# Schematics_Design.net
KiCad netlist of a schematic drawn in EasyEDA
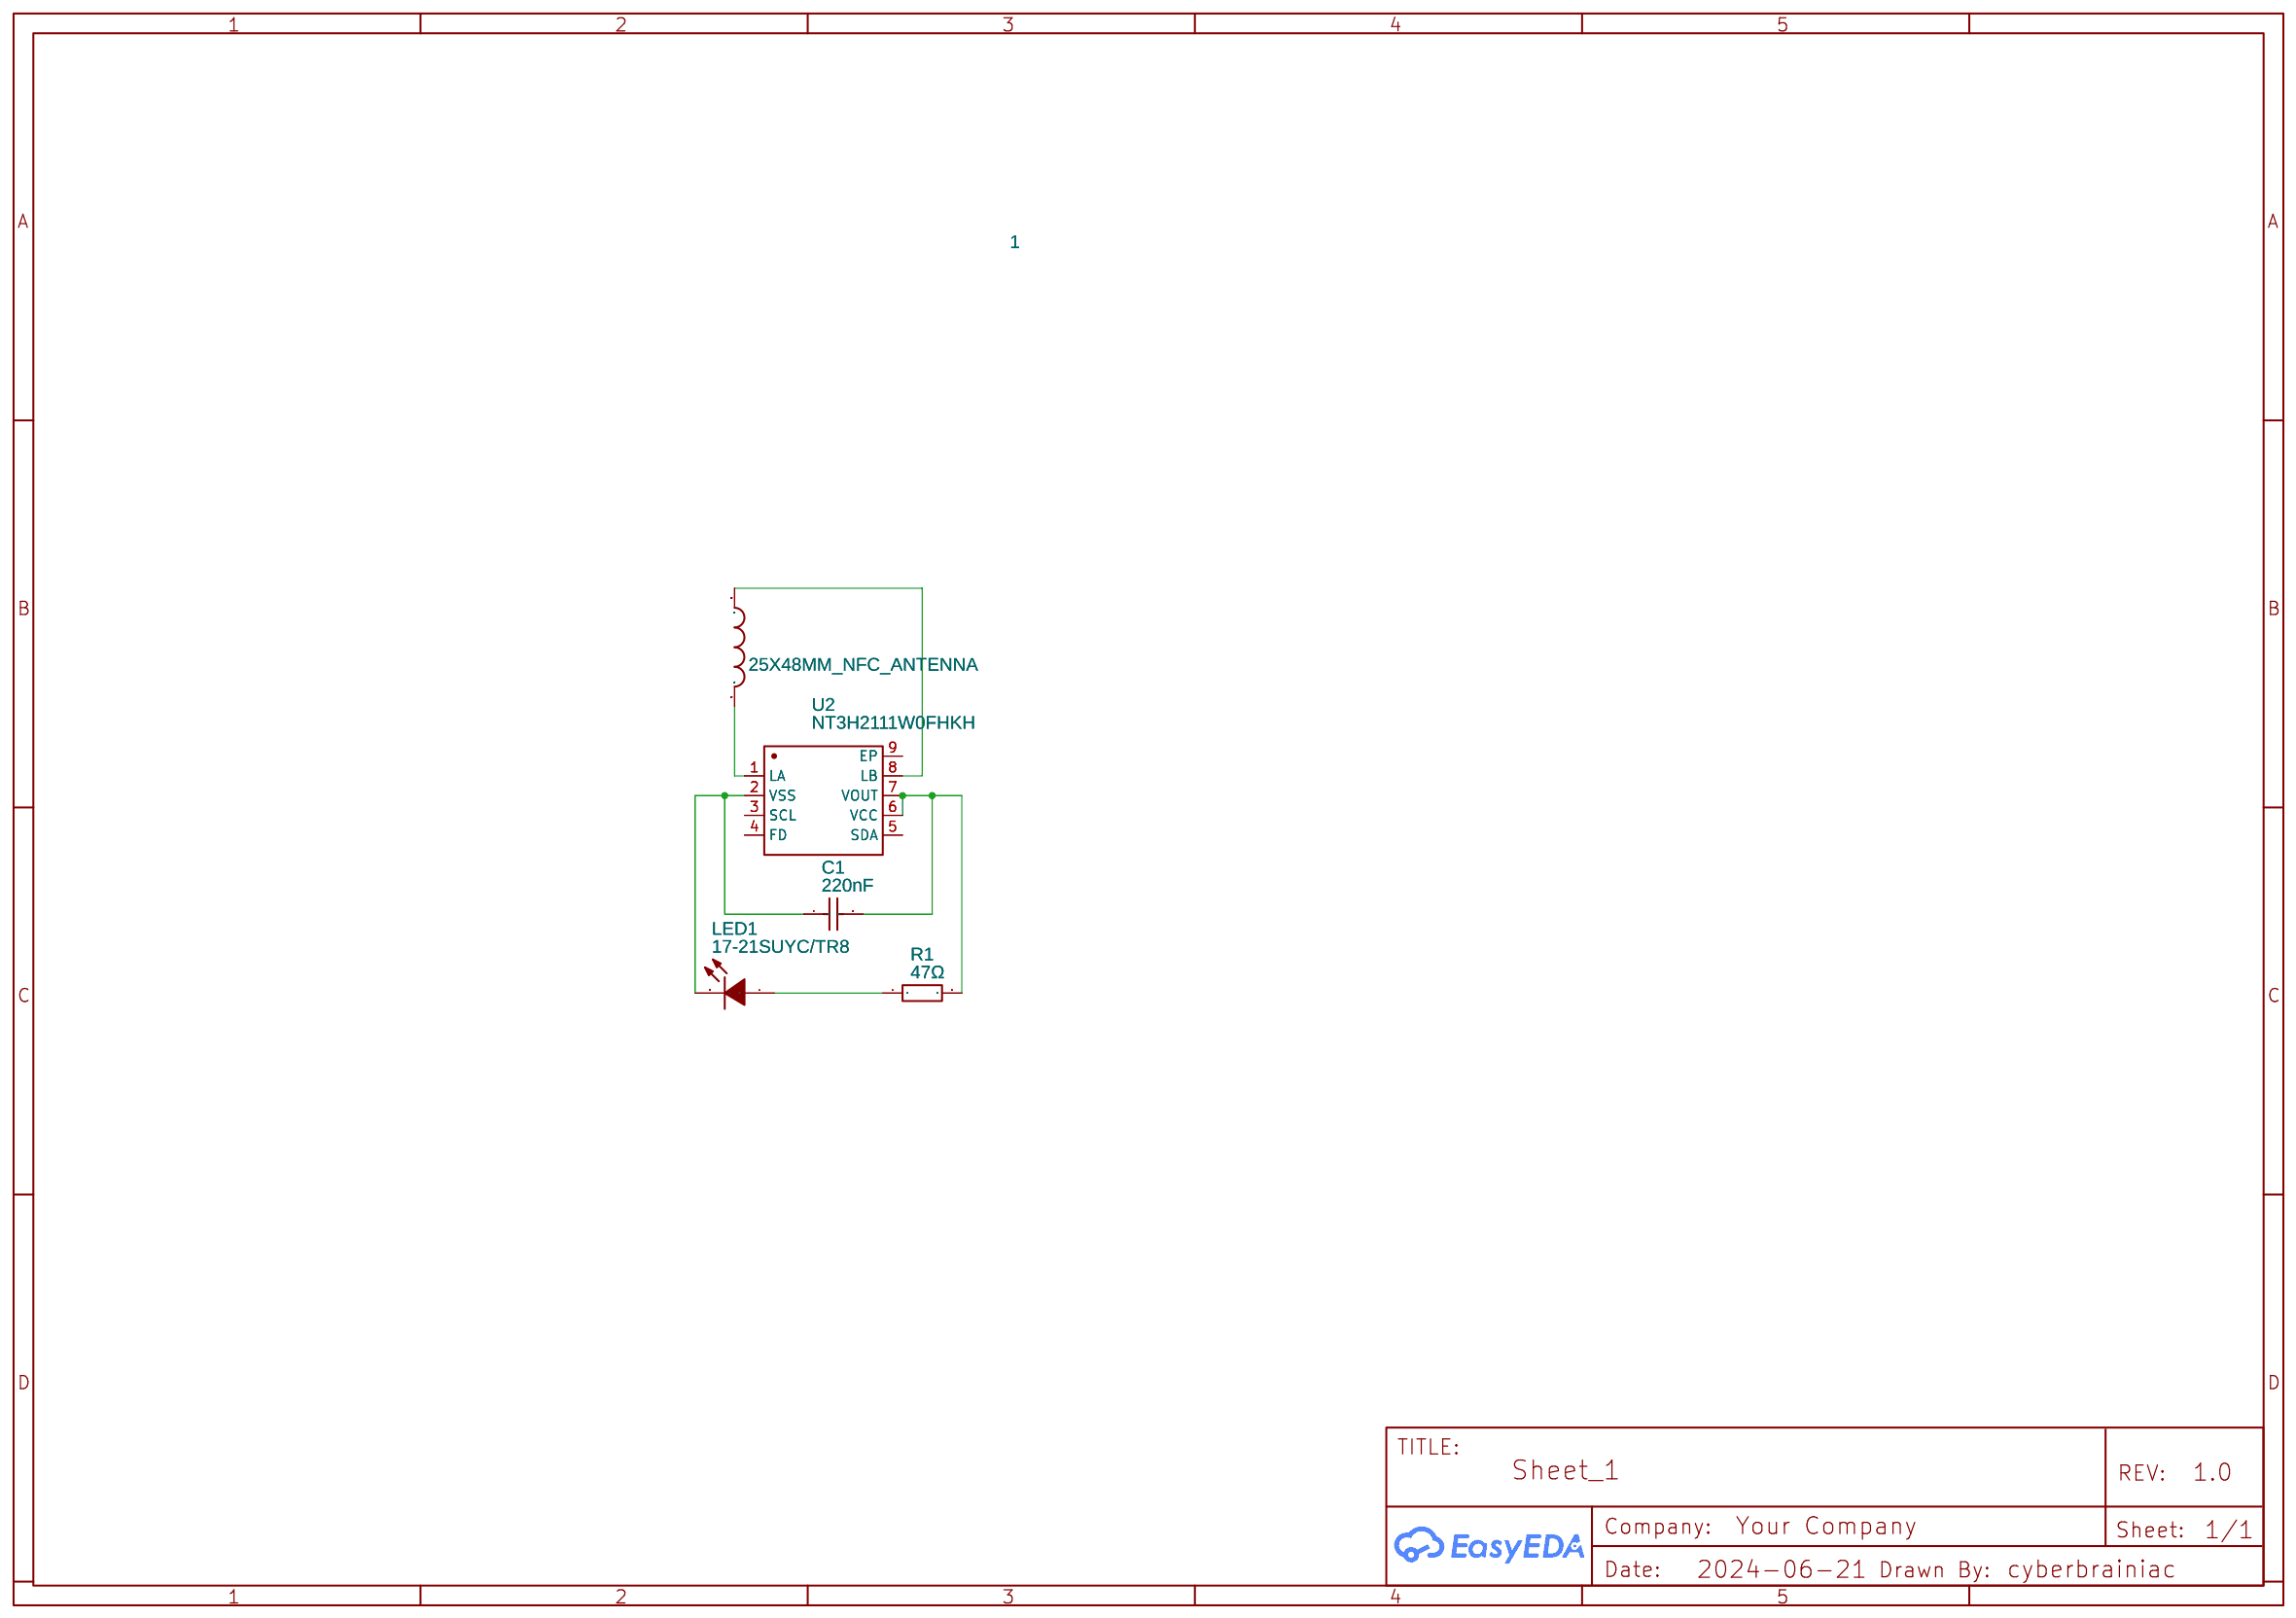
[diagram p0: schematic sheet]

(export (version "E")
  (design (tool "Eeschema 10.0.6"))
  (components
    (comp (ref "1") (value "25X48MM_NFC_ANTENNA") (libsource (lib "") (part "25X48MM_NFC_ANTENNA")))
    (comp (ref "C1")
      (value "220nF")
      (fields
        (field (name "Manufacturer Part") "CL10B224KA8NNNC")
        (field (name "Manufacturer") "SAMSUNG(三星)")
      )
      (libsource (lib "") (part "CL10B224KA8NNNC"))
    )
    (comp (ref "LED1")
      (value "17-21SUYC/TR8")
      (fields (field (name "Manufacturer Part") "KT-0805黄灯") (field (name "Manufacturer") "KENTO"))
      (libsource (lib "") (part "17-21SUYC/TR8"))
    )
    (comp (ref "R1")
      (value "47Ω")
      (fields
        (field (name "Manufacturer Part") "0603WAF470JT5E")
        (field (name "Manufacturer") "UNI-ROYAL(厚声)")
      )
      (libsource (lib "") (part "0603WAF470JT5E"))
    )
    (comp (ref "U2")
      (value "NT3H2111W0FHKH")
      (fields (field (name "Manufacturer") "NXP(恩智浦)"))
      (libsource (lib "") (part "NT3H2111W0FHKH"))
    )
  )
  (nets
    (net (code "1") (name "Net-(LED1-+)") (class "Default")
      (node (ref "LED1") (pin "1") (pinfunction "+_1") (pintype "unspecified"))
      (node (ref "R1") (pin "1") (pinfunction "1_1") (pintype "input"))
    )
    (net (code "2") (name "Net-(LED1--)") (class "Default")
      (node (ref "C1") (pin "1") (pinfunction "1_1") (pintype "input"))
      (node (ref "LED1") (pin "2") (pinfunction "-_2") (pintype "unspecified"))
      (node (ref "U2") (pin "2") (pinfunction "VSS_2") (pintype "unspecified"))
    )
    (net (code "3") (name "Net-(U2-LA)") (class "Default")
      (node (ref "1") (pin "P$2") (pinfunction "P$2_P$2") (pintype "bidirectional"))
      (node (ref "U2") (pin "1") (pinfunction "LA_1") (pintype "unspecified"))
    )
    (net (code "4") (name "Net-(U2-LB)") (class "Default")
      (node (ref "1") (pin "P$1") (pinfunction "P$1_P$1") (pintype "bidirectional"))
      (node (ref "U2") (pin "8") (pinfunction "LB_8") (pintype "unspecified"))
    )
    (net (code "5") (name "Net-(U2-VCC)") (class "Default")
      (node (ref "C1") (pin "2") (pinfunction "2_2") (pintype "input"))
      (node (ref "R1") (pin "2") (pinfunction "2_2") (pintype "input"))
      (node (ref "U2") (pin "6") (pinfunction "VCC_6") (pintype "unspecified"))
      (node (ref "U2") (pin "7") (pinfunction "VOUT_7") (pintype "unspecified"))
    )
    (net (code "6") (name "unconnected-(U2-EP-Pad9)") (class "Default")
      (node (ref "U2") (pin "9") (pinfunction "EP_9") (pintype "unspecified"))
    )
    (net (code "7") (name "unconnected-(U2-FD-Pad4)") (class "Default")
      (node (ref "U2") (pin "4") (pinfunction "FD_4") (pintype "unspecified"))
    )
    (net (code "8") (name "unconnected-(U2-SCL-Pad3)") (class "Default")
      (node (ref "U2") (pin "3") (pinfunction "SCL_3") (pintype "unspecified"))
    )
    (net (code "9") (name "unconnected-(U2-SDA-Pad5)") (class "Default")
      (node (ref "U2") (pin "5") (pinfunction "SDA_5") (pintype "unspecified"))
    )
  )
)
